# E-BookReaderSchematicUdateanuAndreea.net
KiCad netlist of a schematic drawn in EAGLE
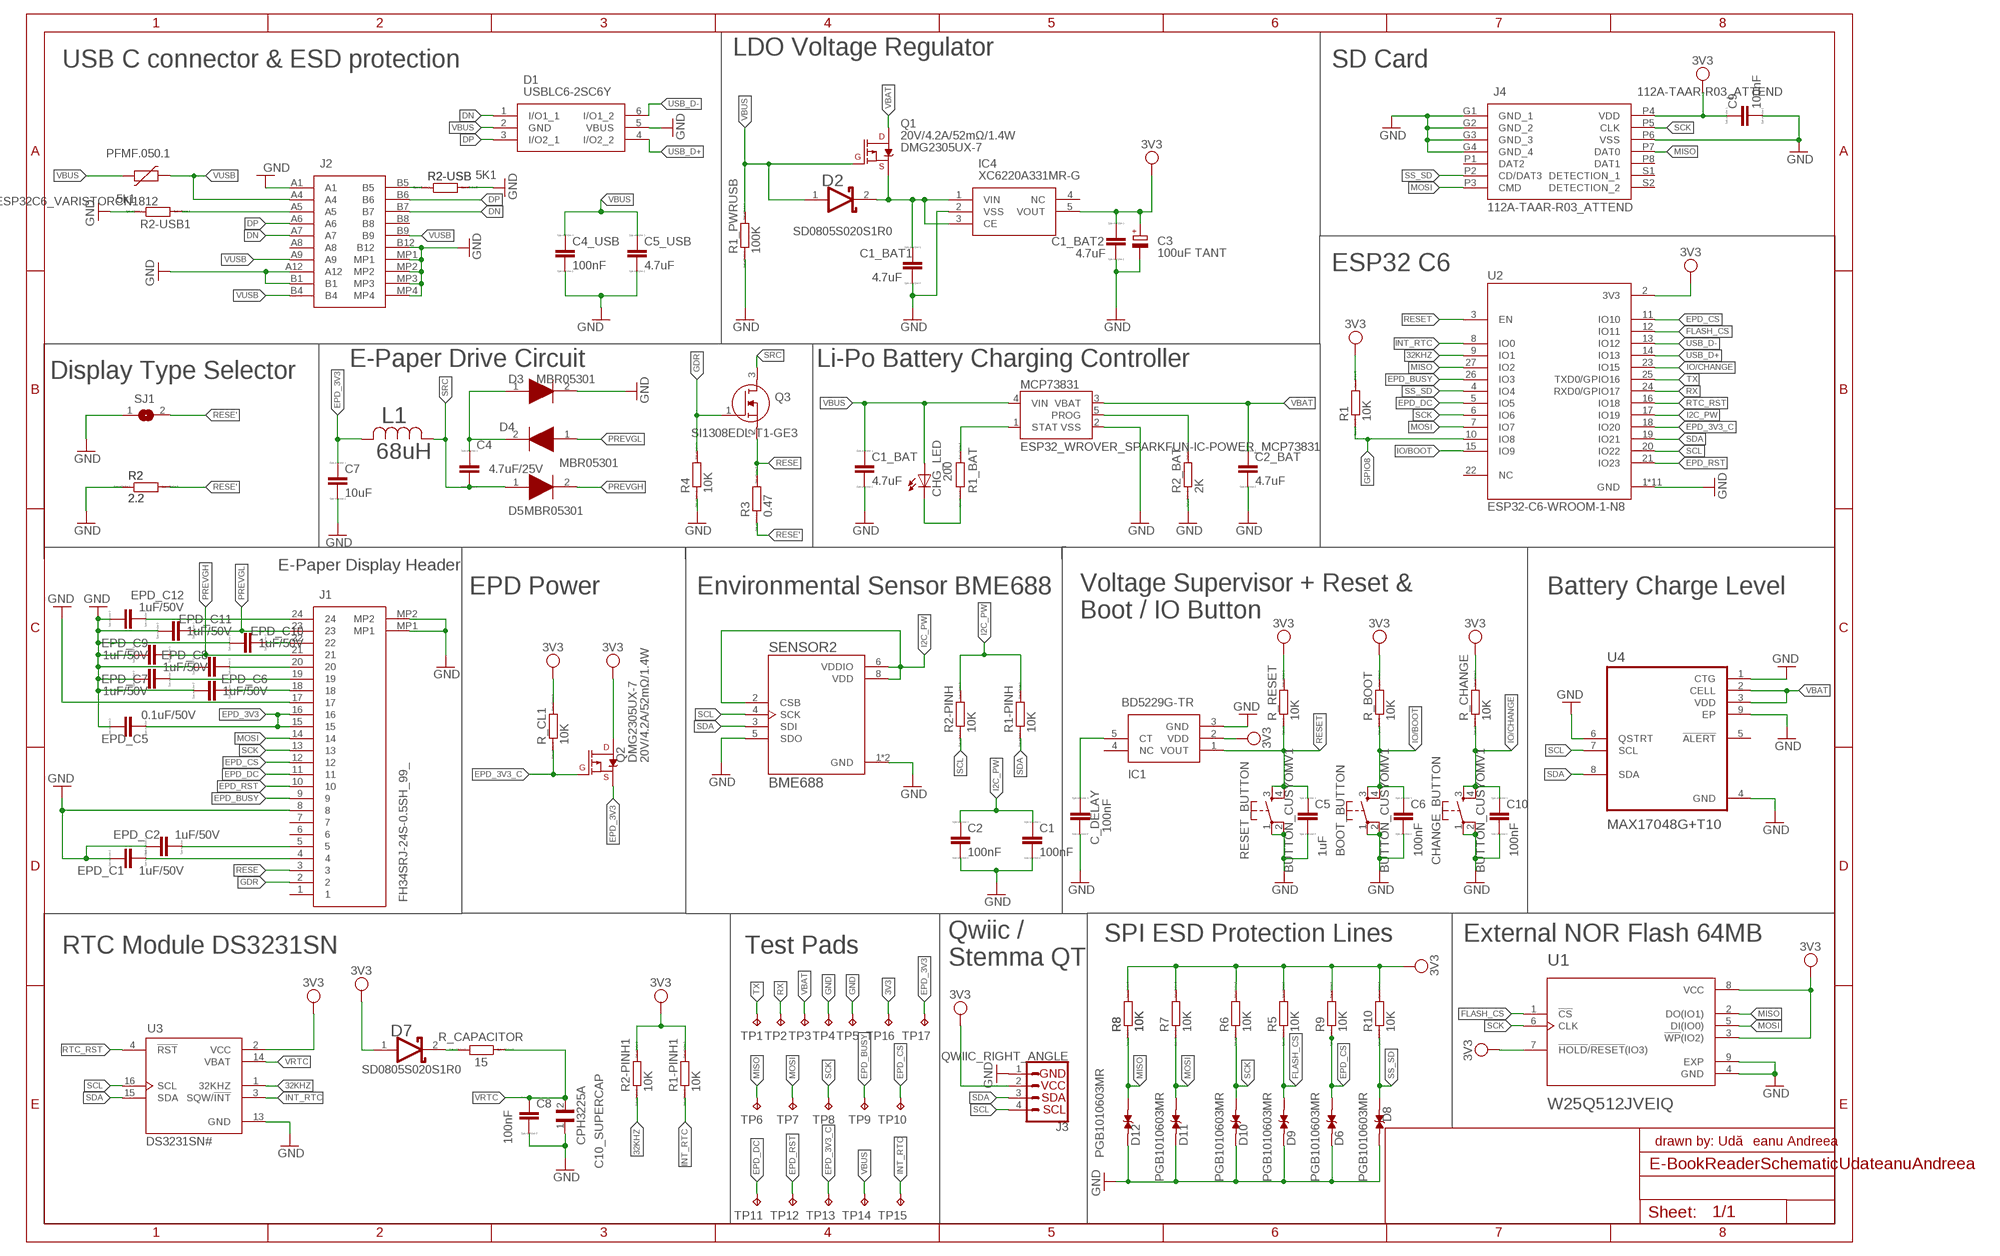
[diagram p0: schematic, sheet 1]

(export (version "E")
  (design (tool "Eeschema 10.0.6"))
  (components
    (comp (ref "BOOT_BUTTON")
      (value "BUTTON_CUSYOMV1")
      (footprint "eagle-import:MYBUTTON")
      (libsource (lib "eagle-import") (part "BUTTON_CUSYOMV1"))
    )
    (comp (ref "C1")
      (value "100nF")
      (footprint "eagle-import:EAGLE-LTSPICE_C0402")
      (libsource (lib "eagle-import") (part "EAGLE-LTSPICE_CC0402"))
    )
    (comp (ref "C1_BAT")
      (value "4.7uF")
      (footprint "eagle-import:EAGLE-LTSPICE_C0402")
      (libsource (lib "eagle-import") (part "EAGLE-LTSPICE_CC0402"))
    )
    (comp (ref "C1_BAT1")
      (value "4.7uF")
      (footprint "eagle-import:EAGLE-LTSPICE_C0402")
      (libsource (lib "eagle-import") (part "EAGLE-LTSPICE_CC0402"))
    )
    (comp (ref "C1_BAT2")
      (value "4.7uF")
      (footprint "eagle-import:EAGLE-LTSPICE_C0402")
      (libsource (lib "eagle-import") (part "EAGLE-LTSPICE_CC0402"))
    )
    (comp (ref "C2")
      (value "100nF")
      (footprint "eagle-import:EAGLE-LTSPICE_C0402")
      (libsource (lib "eagle-import") (part "EAGLE-LTSPICE_CC0402"))
    )
    (comp (ref "C2_BAT")
      (value "4.7uF")
      (footprint "eagle-import:EAGLE-LTSPICE_C0402")
      (libsource (lib "eagle-import") (part "EAGLE-LTSPICE_CC0402"))
    )
    (comp (ref "C3")
      (value "100uF TANT")
      (footprint "eagle-import:RCL_CT3528")
      (libsource (lib "eagle-import") (part "RCL_CPOL-EUCT3528"))
    )
    (comp (ref "C4")
      (value "4.7uF/25V")
      (footprint "eagle-import:EAGLE-LTSPICE_C0402")
      (libsource (lib "eagle-import") (part "EAGLE-LTSPICE_CC0402"))
    )
    (comp (ref "C4_USB")
      (value "100nF")
      (footprint "eagle-import:ESP32_WROVER_EAGLE-LTSPICE_C0402")
      (libsource (lib "eagle-import") (part "ESP32_WROVER_EAGLE-LTSPICE_CC0402"))
    )
    (comp (ref "C5")
      (value "1uF")
      (footprint "eagle-import:EAGLE-LTSPICE_C0402")
      (libsource (lib "eagle-import") (part "EAGLE-LTSPICE_CC0402"))
    )
    (comp (ref "C5_USB")
      (value "4.7uF")
      (footprint "eagle-import:ESP32_WROVER_EAGLE-LTSPICE_C0402")
      (libsource (lib "eagle-import") (part "ESP32_WROVER_EAGLE-LTSPICE_CC0402"))
    )
    (comp (ref "C6")
      (value "100nF")
      (footprint "eagle-import:EAGLE-LTSPICE_C0402")
      (libsource (lib "eagle-import") (part "EAGLE-LTSPICE_CC0402"))
    )
    (comp (ref "C7")
      (value "10uF")
      (footprint "eagle-import:EAGLE-LTSPICE_C0402")
      (libsource (lib "eagle-import") (part "EAGLE-LTSPICE_CC0402"))
    )
    (comp (ref "C8")
      (value "100nF")
      (footprint "eagle-import:EAGLE-LTSPICE_C0402")
      (libsource (lib "eagle-import") (part "EAGLE-LTSPICE_CC0402"))
    )
    (comp (ref "C9")
      (value "100nF")
      (footprint "eagle-import:ESP32_WROVER_EAGLE-LTSPICE_C0402")
      (libsource (lib "eagle-import") (part "ESP32_WROVER_EAGLE-LTSPICE_CC0402"))
    )
    (comp (ref "C10")
      (value "100nF")
      (footprint "eagle-import:EAGLE-LTSPICE_C0402")
      (libsource (lib "eagle-import") (part "EAGLE-LTSPICE_CC0402"))
    )
    (comp (ref "C10_SUPERCAP")
      (value "CPH3225A")
      (footprint "eagle-import:CAPCP3225X100N")
      (fields (field (name "MF") "Seiko Instruments"))
      (libsource (lib "eagle-import") (part "CPH3225A"))
    )
    (comp (ref "CHANGE_BUTTON")
      (value "BUTTON_CUSYOMV1")
      (footprint "eagle-import:MYBUTTON")
      (libsource (lib "eagle-import") (part "BUTTON_CUSYOMV1"))
    )
    (comp (ref "CHG_LED")
      (value "ADAFRUIT_LEDCHIP-LED0603")
      (footprint "eagle-import:ADAFRUIT_CHIP-LED0603")
      (libsource (lib "eagle-import") (part "ADAFRUIT_LEDCHIP-LED0603"))
    )
    (comp (ref "C_DELAY")
      (value "100nF")
      (footprint "eagle-import:EAGLE-LTSPICE_C0402")
      (libsource (lib "eagle-import") (part "EAGLE-LTSPICE_CC0402"))
    )
    (comp (ref "D1")
      (value "USBLC6-2SC6Y")
      (footprint "eagle-import:SOT95P280X145-6N")
      (fields (field (name "MF") "STMicroelectronics"))
      (libsource (lib "eagle-import") (part "USBLC6-2SC6Y"))
    )
    (comp (ref "D2")
      (value "SD0805S020S1R0")
      (footprint "eagle-import:ESP32_WROVER_AVX---SD0805S020S1R0_AVX_SD0805S020S1R0_0")
      (libsource (lib "eagle-import") (part "ESP32_WROVER_AVX---SD0805S020S1R0_AVX_SD0805S020S1R0_0_0"))
    )
    (comp (ref "D3")
      (value "MBR05301")
      (footprint "eagle-import:SOD3716X135N")
      (libsource (lib "eagle-import") (part "MBR05301"))
    )
    (comp (ref "D4")
      (value "MBR05301")
      (footprint "eagle-import:SOD3716X135N")
      (libsource (lib "eagle-import") (part "MBR05301"))
    )
    (comp (ref "D5")
      (value "MBR05301")
      (footprint "eagle-import:SOD3716X135N")
      (libsource (lib "eagle-import") (part "MBR05301"))
    )
    (comp (ref "D6")
      (value "PGB1010603MR")
      (footprint "eagle-import:DIOC1608X36N")
      (fields (field (name "MF") "Littelfuse Inc."))
      (libsource (lib "eagle-import") (part "PGB1010603MR"))
    )
    (comp (ref "D7")
      (value "SD0805S020S1R0")
      (footprint "eagle-import:ESP32_WROVER_AVX---SD0805S020S1R0_AVX_SD0805S020S1R0_0")
      (libsource (lib "eagle-import") (part "ESP32_WROVER_AVX---SD0805S020S1R0_AVX_SD0805S020S1R0_0_0"))
    )
    (comp (ref "D8")
      (value "PGB1010603MR")
      (footprint "eagle-import:DIOC1608X36N")
      (fields (field (name "MF") "Littelfuse Inc."))
      (libsource (lib "eagle-import") (part "PGB1010603MR"))
    )
    (comp (ref "D9")
      (value "PGB1010603MR")
      (footprint "eagle-import:DIOC1608X36N")
      (fields (field (name "MF") "Littelfuse Inc."))
      (libsource (lib "eagle-import") (part "PGB1010603MR"))
    )
    (comp (ref "D10")
      (value "PGB1010603MR")
      (footprint "eagle-import:DIOC1608X36N")
      (fields (field (name "MF") "Littelfuse Inc."))
      (libsource (lib "eagle-import") (part "PGB1010603MR"))
    )
    (comp (ref "D11")
      (value "PGB1010603MR")
      (footprint "eagle-import:DIOC1608X36N")
      (fields (field (name "MF") "Littelfuse Inc."))
      (libsource (lib "eagle-import") (part "PGB1010603MR"))
    )
    (comp (ref "D12")
      (value "PGB1010603MR")
      (footprint "eagle-import:DIOC1608X36N")
      (fields (field (name "MF") "Littelfuse Inc."))
      (libsource (lib "eagle-import") (part "PGB1010603MR"))
    )
    (comp (ref "EPD_C1")
      (value "1uF/50V")
      (footprint "eagle-import:EAGLE-LTSPICE_C0402")
      (libsource (lib "eagle-import") (part "EAGLE-LTSPICE_CC0402"))
    )
    (comp (ref "EPD_C2")
      (value "1uF/50V")
      (footprint "eagle-import:EAGLE-LTSPICE_C0402")
      (libsource (lib "eagle-import") (part "EAGLE-LTSPICE_CC0402"))
    )
    (comp (ref "EPD_C5")
      (value "0.1uF/50V")
      (footprint "eagle-import:EAGLE-LTSPICE_C0402")
      (libsource (lib "eagle-import") (part "EAGLE-LTSPICE_CC0402"))
    )
    (comp (ref "EPD_C6")
      (value "1uF/50V")
      (footprint "eagle-import:EAGLE-LTSPICE_C0402")
      (libsource (lib "eagle-import") (part "EAGLE-LTSPICE_CC0402"))
    )
    (comp (ref "EPD_C7")
      (value "1uF/50V")
      (footprint "eagle-import:EAGLE-LTSPICE_C0402")
      (libsource (lib "eagle-import") (part "EAGLE-LTSPICE_CC0402"))
    )
    (comp (ref "EPD_C8")
      (value "1uF/50V")
      (footprint "eagle-import:EAGLE-LTSPICE_C0402")
      (libsource (lib "eagle-import") (part "EAGLE-LTSPICE_CC0402"))
    )
    (comp (ref "EPD_C9")
      (value "1uF/50V")
      (footprint "eagle-import:EAGLE-LTSPICE_C0402")
      (libsource (lib "eagle-import") (part "EAGLE-LTSPICE_CC0402"))
    )
    (comp (ref "EPD_C10")
      (value "1uF/50V")
      (footprint "eagle-import:EAGLE-LTSPICE_C0402")
      (libsource (lib "eagle-import") (part "EAGLE-LTSPICE_CC0402"))
    )
    (comp (ref "EPD_C11")
      (value "1uF/50V")
      (footprint "eagle-import:EAGLE-LTSPICE_C0402")
      (libsource (lib "eagle-import") (part "EAGLE-LTSPICE_CC0402"))
    )
    (comp (ref "EPD_C12")
      (value "1uF/50V")
      (footprint "eagle-import:EAGLE-LTSPICE_C0402")
      (libsource (lib "eagle-import") (part "EAGLE-LTSPICE_CC0402"))
    )
    (comp (ref "IC1")
      (value "BD5229G-TR")
      (footprint "eagle-import:SOT95P280X125-5N")
      (fields (field (name "MOUSER_PART_NUMBER") "755-BD5229G-TR"))
      (libsource (lib "eagle-import") (part "BD5229G-TR"))
    )
    (comp (ref "IC4")
      (value "XC6220A331MR-G")
      (footprint "eagle-import:SOT95P280X120-5N")
      (fields (field (name "MOUSER_PART_NUMBER") "865-XC6220A331MR-G"))
      (libsource (lib "eagle-import") (part "XC6220A331MR-G"))
    )
    (comp (ref "J1")
      (value "FH34SRJ-24S-0.5SH_99_")
      (footprint "eagle-import:FH34SRJ24S05SH99")
      (fields
        (field (name "MANUFACTURER_PART_NUMBER") "FH34SRJ-24S-0.5SH(99)")
        (field (name "MOUSER_PART_NUMBER") "798-FH34SRJ24S05SH99")
      )
      (libsource (lib "eagle-import") (part "FH34SRJ-24S-0.5SH_99_"))
    )
    (comp (ref "J2")
      (value "SAMACSYS_PARTS_USB4110-GF-A")
      (footprint "eagle-import:SAMACSYS_PARTS_USB4110GFA")
      (fields
        (field (name "MANUFACTURER_PART_NUMBER") "USB4110-GF-A")
        (field (name "MOUSER_PART_NUMBER") "640-USB4110-GF-A")
      )
      (libsource (lib "eagle-import") (part "SAMACSYS_PARTS_USB4110-GF-A"))
    )
    (comp (ref "J3")
      (value "QWIIC_RIGHT_ANGLE")
      (footprint "eagle-import:JST04_1MM_RA")
      (libsource (lib "eagle-import") (part "QWIIC_CONNECTORJS-1MM"))
    )
    (comp (ref "J4")
      (value "112A-TAAR-R03_ATTEND")
      (footprint "eagle-import:112ATAARR03ATTEND")
      (fields (field (name "MANUFACTURER_PART_NUMBER") "112A-TAAR-R03 ATTEND"))
      (libsource (lib "eagle-import") (part "112A-TAAR-R03_ATTEND"))
    )
    (comp (ref "L1")
      (value "68uH")
      (footprint "eagle-import:IND_4828-WE-TPC_WRE")
      (fields
        (field (name "MANUFACTURER_PART_NUMBER") "744043680")
        (field (name "COPYRIGHT") "Copyright (C) 2024 Ultra Librarian. All rights reserved.")
      )
      (libsource (lib "eagle-import") (part "744043680IND_4828-WE-TPC_WRE"))
    )
    (comp (ref "MCP73831")
      (value "ESP32_WROVER_SPARKFUN-IC-POWER_MCP73831")
      (footprint "eagle-import:ESP32_WROVER_SPARKFUN-IC-POWER_SOT23-5")
      (libsource (lib "eagle-import") (part "ESP32_WROVER_SPARKFUN-IC-POWER_MCP73831"))
    )
    (comp (ref "PFMF.050.1")
      (value "ESP32C6_VARISTORCN1812")
      (footprint "eagle-import:ESP32C6_VARISTOR_CT_CN1812")
      (libsource (lib "eagle-import") (part "ESP32C6_VARISTORCN1812"))
    )
    (comp (ref "Q1")
      (value "20V/4.2A/52mΩ/1.4W")
      (footprint "eagle-import:ESP32_WROVER_SPARKFUN-DISCRETESEMI_SOT23-3")
      (libsource (lib "eagle-import") (part "ESP32_WROVER_SPARKFUN-DISCRETESEMI_MOSFET_PCH-DMG2305UX-7"))
    )
    (comp (ref "Q2")
      (value "20V/4.2A/52mΩ/1.4W")
      (footprint "eagle-import:ESP32_WROVER_SPARKFUN-DISCRETESEMI_SOT23-3")
      (libsource (lib "eagle-import") (part "ESP32_WROVER_SPARKFUN-DISCRETESEMI_MOSFET_PCH-DMG2305UX-7"))
    )
    (comp (ref "Q3")
      (value "SI1308EDL-T1-GE3")
      (footprint "eagle-import:SOT65P210X110-3N")
      (fields (field (name "MF") "Vishay Siliconix"))
      (libsource (lib "eagle-import") (part "SI1308EDL-T1-GE3"))
    )
    (comp (ref "R1")
      (value "10K")
      (footprint "eagle-import:ESP32_WROVER_EAGLE-LTSPICE_R0402")
      (libsource (lib "eagle-import") (part "ESP32_WROVER_EAGLE-LTSPICE_RR0402"))
    )
    (comp (ref "R1-PINH")
      (value "10K")
      (footprint "eagle-import:ESP32_WROVER_EAGLE-LTSPICE_R0402")
      (libsource (lib "eagle-import") (part "ESP32_WROVER_EAGLE-LTSPICE_RR0402"))
    )
    (comp (ref "R1-PINH1")
      (value "10K")
      (footprint "eagle-import:ESP32_WROVER_EAGLE-LTSPICE_R0402")
      (libsource (lib "eagle-import") (part "ESP32_WROVER_EAGLE-LTSPICE_RR0402"))
    )
    (comp (ref "R1_BAT")
      (value "200")
      (footprint "eagle-import:ESP32_WROVER_EAGLE-LTSPICE_R0402")
      (libsource (lib "eagle-import") (part "ESP32_WROVER_EAGLE-LTSPICE_RR0402"))
    )
    (comp (ref "R1_PWRUSB")
      (value "100K")
      (footprint "eagle-import:ESP32_WROVER_EAGLE-LTSPICE_R0402")
      (libsource (lib "eagle-import") (part "ESP32_WROVER_EAGLE-LTSPICE_RR0402"))
    )
    (comp (ref "R2")
      (value "2.2")
      (footprint "eagle-import:ESP32_WROVER_EAGLE-LTSPICE_R0402")
      (libsource (lib "eagle-import") (part "ESP32_WROVER_EAGLE-LTSPICE_RR0402"))
    )
    (comp (ref "R2-PINH")
      (value "10K")
      (footprint "eagle-import:ESP32_WROVER_EAGLE-LTSPICE_R0402")
      (libsource (lib "eagle-import") (part "ESP32_WROVER_EAGLE-LTSPICE_RR0402"))
    )
    (comp (ref "R2-PINH1")
      (value "10K")
      (footprint "eagle-import:ESP32_WROVER_EAGLE-LTSPICE_R0402")
      (libsource (lib "eagle-import") (part "ESP32_WROVER_EAGLE-LTSPICE_RR0402"))
    )
    (comp (ref "R2-USB")
      (value "5K1")
      (footprint "eagle-import:ESP32_WROVER_EAGLE-LTSPICE_R0402")
      (libsource (lib "eagle-import") (part "ESP32_WROVER_EAGLE-LTSPICE_RR0402"))
    )
    (comp (ref "R2-USB1")
      (value "5k1")
      (footprint "eagle-import:ESP32_WROVER_EAGLE-LTSPICE_R0402")
      (libsource (lib "eagle-import") (part "ESP32_WROVER_EAGLE-LTSPICE_RR0402"))
    )
    (comp (ref "R2_BAT")
      (value "2K")
      (footprint "eagle-import:ESP32_WROVER_EAGLE-LTSPICE_R0402")
      (libsource (lib "eagle-import") (part "ESP32_WROVER_EAGLE-LTSPICE_RR0402"))
    )
    (comp (ref "R3")
      (value "0.47")
      (footprint "eagle-import:ESP32_WROVER_EAGLE-LTSPICE_R0402")
      (libsource (lib "eagle-import") (part "ESP32_WROVER_EAGLE-LTSPICE_RR0402"))
    )
    (comp (ref "R4")
      (value "10K")
      (footprint "eagle-import:ESP32_WROVER_EAGLE-LTSPICE_R0402")
      (libsource (lib "eagle-import") (part "ESP32_WROVER_EAGLE-LTSPICE_RR0402"))
    )
    (comp (ref "R5")
      (value "10K")
      (footprint "eagle-import:ESP32_WROVER_EAGLE-LTSPICE_R0402")
      (libsource (lib "eagle-import") (part "ESP32_WROVER_EAGLE-LTSPICE_RR0402"))
    )
    (comp (ref "R6")
      (value "10K")
      (footprint "eagle-import:ESP32_WROVER_EAGLE-LTSPICE_R0402")
      (libsource (lib "eagle-import") (part "ESP32_WROVER_EAGLE-LTSPICE_RR0402"))
    )
    (comp (ref "R7")
      (value "10K")
      (footprint "eagle-import:ESP32_WROVER_EAGLE-LTSPICE_R0402")
      (libsource (lib "eagle-import") (part "ESP32_WROVER_EAGLE-LTSPICE_RR0402"))
    )
    (comp (ref "R8")
      (value "10K")
      (footprint "eagle-import:ESP32_WROVER_EAGLE-LTSPICE_R0402")
      (libsource (lib "eagle-import") (part "ESP32_WROVER_EAGLE-LTSPICE_RR0402"))
    )
    (comp (ref "R9")
      (value "10K")
      (footprint "eagle-import:ESP32_WROVER_EAGLE-LTSPICE_R0402")
      (libsource (lib "eagle-import") (part "ESP32_WROVER_EAGLE-LTSPICE_RR0402"))
    )
    (comp (ref "R10")
      (value "10K")
      (footprint "eagle-import:ESP32_WROVER_EAGLE-LTSPICE_R0402")
      (libsource (lib "eagle-import") (part "ESP32_WROVER_EAGLE-LTSPICE_RR0402"))
    )
    (comp (ref "RESET_BUTTON")
      (value "BUTTON_CUSYOMV1")
      (footprint "eagle-import:MYBUTTON")
      (libsource (lib "eagle-import") (part "BUTTON_CUSYOMV1"))
    )
    (comp (ref "R_BOOT")
      (value "10K")
      (footprint "eagle-import:ESP32_WROVER_EAGLE-LTSPICE_R0402")
      (libsource (lib "eagle-import") (part "ESP32_WROVER_EAGLE-LTSPICE_RR0402"))
    )
    (comp (ref "R_CAPACITOR")
      (value "15")
      (footprint "eagle-import:ESP32_WROVER_EAGLE-LTSPICE_R0402")
      (libsource (lib "eagle-import") (part "ESP32_WROVER_EAGLE-LTSPICE_RR0402"))
    )
    (comp (ref "R_CHANGE")
      (value "10K")
      (footprint "eagle-import:ESP32_WROVER_EAGLE-LTSPICE_R0402")
      (libsource (lib "eagle-import") (part "ESP32_WROVER_EAGLE-LTSPICE_RR0402"))
    )
    (comp (ref "R_CL1")
      (value "10K")
      (footprint "eagle-import:ESP32_WROVER_EAGLE-LTSPICE_R0402")
      (libsource (lib "eagle-import") (part "ESP32_WROVER_EAGLE-LTSPICE_RR0402"))
    )
    (comp (ref "R_RESET")
      (value "10K")
      (footprint "eagle-import:ESP32_WROVER_EAGLE-LTSPICE_R0402")
      (libsource (lib "eagle-import") (part "ESP32_WROVER_EAGLE-LTSPICE_RR0402"))
    )
    (comp (ref "SENSOR2")
      (value "BME688")
      (footprint "eagle-import:ESP32_WROVER_BME680_PSON80P300X300X100-8N")
      (fields (field (name "MF") "Bosch Sensortec") (field (name "MP") "BME680"))
      (libsource (lib "eagle-import") (part "ESP32_WROVER_BME680_BME680"))
    )
    (comp (ref "SJ1") (value "SJ") (footprint "eagle-import:SJ") (libsource (lib "eagle-import") (part "SJ")))
    (comp (ref "TP1")
      (value "TPTP20R")
      (footprint "eagle-import:TP20R")
      (libsource (lib "eagle-import") (part "TP"))
    )
    (comp (ref "TP2")
      (value "TP")
      (footprint "eagle-import:TP20R")
      (libsource (lib "eagle-import") (part "TP"))
    )
    (comp (ref "TP3")
      (value "TP")
      (footprint "eagle-import:TP20R")
      (libsource (lib "eagle-import") (part "TP"))
    )
    (comp (ref "TP4")
      (value "TP")
      (footprint "eagle-import:TP20R")
      (libsource (lib "eagle-import") (part "TP"))
    )
    (comp (ref "TP5")
      (value "TP")
      (footprint "eagle-import:TP20R")
      (libsource (lib "eagle-import") (part "TP"))
    )
    (comp (ref "TP6")
      (value "TP")
      (footprint "eagle-import:TP20R")
      (libsource (lib "eagle-import") (part "TP"))
    )
    (comp (ref "TP7")
      (value "TP")
      (footprint "eagle-import:TP20R")
      (libsource (lib "eagle-import") (part "TP"))
    )
    (comp (ref "TP8")
      (value "TP")
      (footprint "eagle-import:TP20R")
      (libsource (lib "eagle-import") (part "TP"))
    )
    (comp (ref "TP9")
      (value "TP")
      (footprint "eagle-import:TP20R")
      (libsource (lib "eagle-import") (part "TP"))
    )
    (comp (ref "TP10")
      (value "TP")
      (footprint "eagle-import:TP20R")
      (libsource (lib "eagle-import") (part "TP"))
    )
    (comp (ref "TP11")
      (value "TP")
      (footprint "eagle-import:TP20R")
      (libsource (lib "eagle-import") (part "TP"))
    )
    (comp (ref "TP12")
      (value "TP")
      (footprint "eagle-import:TP20R")
      (libsource (lib "eagle-import") (part "TP"))
    )
    (comp (ref "TP13")
      (value "TP")
      (footprint "eagle-import:TP20R")
      (libsource (lib "eagle-import") (part "TP"))
    )
    (comp (ref "TP14")
      (value "TP")
      (footprint "eagle-import:TP20R")
      (libsource (lib "eagle-import") (part "TP"))
    )
    (comp (ref "TP15")
      (value "TP")
      (footprint "eagle-import:TP20R")
      (libsource (lib "eagle-import") (part "TP"))
    )
    (comp (ref "TP16")
      (value "TP")
      (footprint "eagle-import:TP20R")
      (libsource (lib "eagle-import") (part "TP"))
    )
    (comp (ref "TP17")
      (value "TP")
      (footprint "eagle-import:TP20R")
      (libsource (lib "eagle-import") (part "TP"))
    )
    (comp (ref "U1")
      (value "W25Q512JVEIQ")
      (footprint "eagle-import:SON127P600X800X80-9N")
      (fields (field (name "MF") "Winbond Electronics"))
      (libsource (lib "eagle-import") (part "W25Q512JVEIQ"))
    )
    (comp (ref "U2")
      (value "ESP32-C6-WROOM-1-N8")
      (footprint "eagle-import:XCVR_ESP32-C6-WROOM-1-N8")
      (fields (field (name "MF") "Espressif Systems"))
      (libsource (lib "eagle-import") (part "ESP32-C6-WROOM-1-N8"))
    )
    (comp (ref "U3")
      (value "DS3231SN#")
      (footprint "eagle-import:SOIC127P1032X265-16N")
      (fields (field (name "MF") "Analog Devices"))
      (libsource (lib "eagle-import") (part "DS3231SN#"))
    )
    (comp (ref "U4")
      (value "MAX17048G+T10")
      (footprint "eagle-import:SON50P200X200X80-9N")
      (fields (field (name "MF") "Analog Devices"))
      (libsource (lib "eagle-import") (part "MAX17048G+T10"))
    )
  )
  (nets
    (net (code "1") (name "3V3") (class "Default")
      (node (ref "C1_BAT2") (pin "1") (pinfunction "1_1") (pintype "passive"))
      (node (ref "C3") (pin "+") (pinfunction "+_+") (pintype "passive"))
      (node (ref "C9") (pin "1") (pinfunction "1_1") (pintype "passive"))
      (node (ref "D7") (pin "1") (pinfunction "ANODE_1") (pintype "bidirectional"))
      (node (ref "IC1") (pin "2") (pinfunction "VDD_2") (pintype "bidirectional"))
      (node (ref "IC4") (pin "5") (pinfunction "VOUT_5") (pintype "bidirectional"))
      (node (ref "J3") (pin "2") (pinfunction "2_2") (pintype "power_in"))
      (node (ref "J4") (pin "P4") (pinfunction "VDD_P4") (pintype "bidirectional"))
      (node (ref "Q2") (pin "3") (pinfunction "D_3") (pintype "bidirectional"))
      (node (ref "R1") (pin "2") (pinfunction "2_2") (pintype "passive"))
      (node (ref "R1-PINH1") (pin "2") (pinfunction "2_2") (pintype "passive"))
      (node (ref "R10") (pin "2") (pinfunction "2_2") (pintype "passive"))
      (node (ref "R2-PINH1") (pin "2") (pinfunction "2_2") (pintype "passive"))
      (node (ref "R5") (pin "2") (pinfunction "2_2") (pintype "passive"))
      (node (ref "R6") (pin "2") (pinfunction "2_2") (pintype "passive"))
      (node (ref "R7") (pin "2") (pinfunction "2_2") (pintype "passive"))
      (node (ref "R8") (pin "2") (pinfunction "2_2") (pintype "passive"))
      (node (ref "R9") (pin "2") (pinfunction "2_2") (pintype "passive"))
      (node (ref "R_BOOT") (pin "2") (pinfunction "2_2") (pintype "passive"))
      (node (ref "R_CHANGE") (pin "2") (pinfunction "2_2") (pintype "passive"))
      (node (ref "R_CL1") (pin "2") (pinfunction "2_2") (pintype "passive"))
      (node (ref "R_RESET") (pin "2") (pinfunction "2_2") (pintype "passive"))
      (node (ref "TP16") (pin "TP") (pinfunction "TP_TP") (pintype "input"))
      (node (ref "U1") (pin "3") (pinfunction "~{WP}(IO2)_3") (pintype "bidirectional"))
      (node (ref "U1") (pin "7") (pinfunction "~{HOLD}/~{RESET}(IO3)_7") (pintype "bidirectional"))
      (node (ref "U1") (pin "8") (pinfunction "VCC_8") (pintype "power_in"))
      (node (ref "U2") (pin "2") (pinfunction "3V3_2") (pintype "power_in"))
      (node (ref "U3") (pin "2") (pinfunction "VCC_2") (pintype "power_in"))
    )
    (net (code "2") (name "32KHZ") (class "Default")
      (node (ref "R2-PINH1") (pin "1") (pinfunction "1_1") (pintype "passive"))
      (node (ref "U2") (pin "9") (pinfunction "IO1_9") (pintype "bidirectional"))
      (node (ref "U3") (pin "1") (pinfunction "32KHZ_1") (pintype "output"))
    )
    (net (code "3") (name "DN") (class "Default")
      (node (ref "D1") (pin "1") (pinfunction "I/O1_1_1") (pintype "bidirectional"))
      (node (ref "J2") (pin "A7") (pinfunction "A7_A7") (pintype "bidirectional"))
      (node (ref "J2") (pin "B7") (pinfunction "B7_B7") (pintype "bidirectional"))
    )
    (net (code "4") (name "DP") (class "Default")
      (node (ref "D1") (pin "3") (pinfunction "I/O2_1_3") (pintype "bidirectional"))
      (node (ref "J2") (pin "A6") (pinfunction "A6_A6") (pintype "bidirectional"))
      (node (ref "J2") (pin "B6") (pinfunction "B6_B6") (pintype "bidirectional"))
    )
    (net (code "5") (name "EPD_3V3") (class "Default")
      (node (ref "C7") (pin "1") (pinfunction "1_1") (pintype "passive"))
      (node (ref "EPD_C5") (pin "1") (pinfunction "1_1") (pintype "passive"))
      (node (ref "J1") (pin "15") (pinfunction "15_15") (pintype "bidirectional"))
      (node (ref "J1") (pin "16") (pinfunction "16_16") (pintype "bidirectional"))
      (node (ref "L1") (pin "2") (pinfunction "2_2") (pintype "passive"))
      (node (ref "Q2") (pin "2") (pinfunction "S_2") (pintype "bidirectional"))
      (node (ref "TP17") (pin "TP") (pinfunction "TP_TP") (pintype "input"))
    )
    (net (code "6") (name "EPD_3V3_C") (class "Default")
      (node (ref "Q2") (pin "1") (pinfunction "G_1") (pintype "bidirectional"))
      (node (ref "R_CL1") (pin "1") (pinfunction "1_1") (pintype "passive"))
      (node (ref "TP13") (pin "TP") (pinfunction "TP_TP") (pintype "input"))
      (node (ref "U2") (pin "18") (pinfunction "IO20_18") (pintype "bidirectional"))
    )
    (net (code "7") (name "EPD_BUSY") (class "Default")
      (node (ref "J1") (pin "9") (pinfunction "9_9") (pintype "bidirectional"))
      (node (ref "TP9") (pin "TP") (pinfunction "TP_TP") (pintype "input"))
      (node (ref "U2") (pin "26") (pinfunction "IO3_26") (pintype "bidirectional"))
    )
    (net (code "8") (name "EPD_CS") (class "Default")
      (node (ref "D6") (pin "2") (pinfunction "2_2") (pintype "passive"))
      (node (ref "J1") (pin "12") (pinfunction "12_12") (pintype "bidirectional"))
      (node (ref "R9") (pin "1") (pinfunction "1_1") (pintype "passive"))
      (node (ref "TP10") (pin "TP") (pinfunction "TP_TP") (pintype "input"))
      (node (ref "U2") (pin "11") (pinfunction "IO10_11") (pintype "bidirectional"))
    )
    (net (code "9") (name "EPD_DC") (class "Default")
      (node (ref "J1") (pin "11") (pinfunction "11_11") (pintype "bidirectional"))
      (node (ref "TP11") (pin "TP") (pinfunction "TP_TP") (pintype "input"))
      (node (ref "U2") (pin "5") (pinfunction "IO5_5") (pintype "bidirectional"))
    )
    (net (code "10") (name "EPD_RST") (class "Default")
      (node (ref "J1") (pin "10") (pinfunction "10_10") (pintype "bidirectional"))
      (node (ref "TP12") (pin "TP") (pinfunction "TP_TP") (pintype "input"))
      (node (ref "U2") (pin "21") (pinfunction "IO23_21") (pintype "bidirectional"))
    )
    (net (code "11") (name "FLASH_CS") (class "Default")
      (node (ref "D9") (pin "2") (pinfunction "2_2") (pintype "passive"))
      (node (ref "R5") (pin "1") (pinfunction "1_1") (pintype "passive"))
      (node (ref "U1") (pin "1") (pinfunction "~{CS}_1") (pintype "input"))
      (node (ref "U2") (pin "12") (pinfunction "IO11_12") (pintype "bidirectional"))
    )
    (net (code "12") (name "GDR") (class "Default")
      (node (ref "J1") (pin "2") (pinfunction "2_2") (pintype "bidirectional"))
      (node (ref "Q3") (pin "1") (pinfunction "G_1") (pintype "bidirectional"))
      (node (ref "R4") (pin "2") (pinfunction "2_2") (pintype "passive"))
    )
    (net (code "13") (name "GND") (class "Default")
      (node (ref "BOOT_BUTTON") (pin "1") (pinfunction "1_1") (pintype "passive"))
      (node (ref "BOOT_BUTTON") (pin "2") (pinfunction "2_2") (pintype "passive"))
      (node (ref "C1") (pin "2") (pinfunction "2_2") (pintype "passive"))
      (node (ref "C10") (pin "2") (pinfunction "2_2") (pintype "passive"))
      (node (ref "C10_SUPERCAP") (pin "1") (pinfunction "1_1") (pintype "passive"))
      (node (ref "C1_BAT") (pin "2") (pinfunction "2_2") (pintype "passive"))
      (node (ref "C1_BAT1") (pin "2") (pinfunction "2_2") (pintype "passive"))
      (node (ref "C1_BAT2") (pin "2") (pinfunction "2_2") (pintype "passive"))
      (node (ref "C2") (pin "2") (pinfunction "2_2") (pintype "passive"))
      (node (ref "C2_BAT") (pin "2") (pinfunction "2_2") (pintype "passive"))
      (node (ref "C3") (pin "-") (pinfunction "-_-") (pintype "passive"))
      (node (ref "C4_USB") (pin "2") (pinfunction "2_2") (pintype "passive"))
      (node (ref "C5") (pin "2") (pinfunction "2_2") (pintype "passive"))
      (node (ref "C5_USB") (pin "2") (pinfunction "2_2") (pintype "passive"))
      (node (ref "C6") (pin "2") (pinfunction "2_2") (pintype "passive"))
      (node (ref "C7") (pin "2") (pinfunction "2_2") (pintype "passive"))
      (node (ref "C8") (pin "2") (pinfunction "2_2") (pintype "passive"))
      (node (ref "C9") (pin "2") (pinfunction "2_2") (pintype "passive"))
      (node (ref "CHANGE_BUTTON") (pin "1") (pinfunction "1_1") (pintype "passive"))
      (node (ref "CHANGE_BUTTON") (pin "2") (pinfunction "2_2") (pintype "passive"))
      (node (ref "C_DELAY") (pin "2") (pinfunction "2_2") (pintype "passive"))
      (node (ref "D1") (pin "5") (pinfunction "VBUS_5") (pintype "bidirectional"))
      (node (ref "D10") (pin "1") (pinfunction "1_1") (pintype "passive"))
      (node (ref "D11") (pin "1") (pinfunction "1_1") (pintype "passive"))
      (node (ref "D12") (pin "1") (pinfunction "1_1") (pintype "passive"))
      (node (ref "D3") (pin "2") (pinfunction "K_2") (pintype "bidirectional"))
      (node (ref "D6") (pin "1") (pinfunction "1_1") (pintype "passive"))
      (node (ref "D8") (pin "1") (pinfunction "1_1") (pintype "passive"))
      (node (ref "D9") (pin "1") (pinfunction "1_1") (pintype "passive"))
      (node (ref "EPD_C1") (pin "2") (pinfunction "2_2") (pintype "passive"))
      (node (ref "EPD_C10") (pin "2") (pinfunction "2_2") (pintype "passive"))
      (node (ref "EPD_C11") (pin "2") (pinfunction "2_2") (pintype "passive"))
      (node (ref "EPD_C12") (pin "2") (pinfunction "2_2") (pintype "passive"))
      (node (ref "EPD_C2") (pin "2") (pinfunction "2_2") (pintype "passive"))
      (node (ref "EPD_C5") (pin "2") (pinfunction "2_2") (pintype "passive"))
      (node (ref "EPD_C6") (pin "2") (pinfunction "2_2") (pintype "passive"))
      (node (ref "EPD_C7") (pin "2") (pinfunction "2_2") (pintype "passive"))
      (node (ref "EPD_C8") (pin "2") (pinfunction "2_2") (pintype "passive"))
      (node (ref "EPD_C9") (pin "2") (pinfunction "2_2") (pintype "passive"))
      (node (ref "IC1") (pin "3") (pinfunction "GND_3") (pintype "bidirectional"))
      (node (ref "IC4") (pin "2") (pinfunction "VSS_2") (pintype "bidirectional"))
      (node (ref "J1") (pin "17") (pinfunction "17_17") (pintype "bidirectional"))
      (node (ref "J1") (pin "8") (pinfunction "8_8") (pintype "bidirectional"))
      (node (ref "J1") (pin "MP1") (pinfunction "MP1_MP1") (pintype "bidirectional"))
      (node (ref "J1") (pin "MP2") (pinfunction "MP2_MP2") (pintype "bidirectional"))
      (node (ref "J2") (pin "A1") (pinfunction "A1_A1") (pintype "bidirectional"))
      (node (ref "J2") (pin "A12") (pinfunction "A12_A12") (pintype "bidirectional"))
      (node (ref "J2") (pin "B1") (pinfunction "B1_B1") (pintype "bidirectional"))
      (node (ref "J2") (pin "B12") (pinfunction "B12_B12") (pintype "bidirectional"))
      (node (ref "J2") (pin "MP1") (pinfunction "MP1_MP1") (pintype "bidirectional"))
      (node (ref "J2") (pin "MP2") (pinfunction "MP2_MP2") (pintype "bidirectional"))
      (node (ref "J2") (pin "MP3") (pinfunction "MP3_MP3") (pintype "bidirectional"))
      (node (ref "J2") (pin "MP4") (pinfunction "MP4_MP4") (pintype "bidirectional"))
      (node (ref "J3") (pin "1") (pinfunction "1_1") (pintype "power_in"))
      (node (ref "J4") (pin "G1") (pinfunction "GND_1_G1") (pintype "bidirectional"))
      (node (ref "J4") (pin "G2") (pinfunction "GND_2_G2") (pintype "bidirectional"))
      (node (ref "J4") (pin "G3") (pinfunction "GND_3_G3") (pintype "bidirectional"))
      (node (ref "J4") (pin "G4") (pinfunction "GND_4_G4") (pintype "bidirectional"))
      (node (ref "J4") (pin "P6") (pinfunction "VSS_P6") (pintype "bidirectional"))
      (node (ref "MCP73831") (pin "2") (pinfunction "VSS_2") (pintype "power_in"))
      (node (ref "R1_PWRUSB") (pin "1") (pinfunction "1_1") (pintype "passive"))
      (node (ref "R2") (pin "1") (pinfunction "1_1") (pintype "passive"))
      (node (ref "R2-USB") (pin "2") (pinfunction "2_2") (pintype "passive"))
      (node (ref "R2-USB1") (pin "1") (pinfunction "1_1") (pintype "passive"))
      (node (ref "R2_BAT") (pin "1") (pinfunction "1_1") (pintype "passive"))
      (node (ref "R4") (pin "1") (pinfunction "1_1") (pintype "passive"))
      (node (ref "RESET_BUTTON") (pin "1") (pinfunction "1_1") (pintype "passive"))
      (node (ref "RESET_BUTTON") (pin "2") (pinfunction "2_2") (pintype "passive"))
      (node (ref "SENSOR2") (pin "1") (pinfunction "GND_1") (pintype "power_in"))
      (node (ref "SENSOR2") (pin "5") (pinfunction "SDO_5") (pintype "bidirectional"))
      (node (ref "SENSOR2") (pin "7") (pinfunction "GND_7") (pintype "power_in"))
      (node (ref "SJ1") (pin "1") (pinfunction "1_1") (pintype "passive"))
      (node (ref "TP4") (pin "TP") (pinfunction "TP_TP") (pintype "input"))
      (node (ref "TP5") (pin "TP") (pinfunction "TP_TP") (pintype "input"))
      (node (ref "U1") (pin "4") (pinfunction "GND_4") (pintype "power_in"))
      (node (ref "U1") (pin "9") (pinfunction "EXP_9") (pintype "passive"))
      (node (ref "U2") (pin "1") (pinfunction "GND_1") (pintype "power_in"))
      (node (ref "U2") (pin "28") (pinfunction "GND_28") (pintype "power_in"))
      (node (ref "U2") (pin "29_1") (pinfunction "GND_29_1") (pintype "power_in"))
      (node (ref "U2") (pin "29_2") (pinfunction "GND_29_2") (pintype "power_in"))
      (node (ref "U2") (pin "29_3") (pinfunction "GND_29_3") (pintype "power_in"))
      (node (ref "U2") (pin "29_4") (pinfunction "GND_29_4") (pintype "power_in"))
      (node (ref "U2") (pin "29_5") (pinfunction "GND_29_5") (pintype "power_in"))
      (node (ref "U2") (pin "29_6") (pinfunction "GND_29_6") (pintype "power_in"))
      (node (ref "U2") (pin "29_7") (pinfunction "GND_29_7") (pintype "power_in"))
      (node (ref "U2") (pin "29_8") (pinfunction "GND_29_8") (pintype "power_in"))
      (node (ref "U2") (pin "29_9") (pinfunction "GND_29_9") (pintype "power_in"))
      (node (ref "U3") (pin "13") (pinfunction "GND_13") (pintype "power_in"))
      (node (ref "U4") (pin "1") (pinfunction "CTG_1") (pintype "power_in"))
      (node (ref "U4") (pin "4") (pinfunction "GND_4") (pintype "power_in"))
      (node (ref "U4") (pin "6") (pinfunction "QSTRT_6") (pintype "input"))
      (node (ref "U4") (pin "9") (pinfunction "EP_9") (pintype "power_in"))
    )
    (net (code "14") (name "GPIO8") (class "Default")
      (node (ref "R1") (pin "1") (pinfunction "1_1") (pintype "passive"))
      (node (ref "U2") (pin "10") (pinfunction "IO8_10") (pintype "bidirectional"))
    )
    (net (code "15") (name "I2C_PW") (class "Default")
      (node (ref "C1") (pin "1") (pinfunction "1_1") (pintype "passive"))
      (node (ref "C2") (pin "1") (pinfunction "1_1") (pintype "passive"))
      (node (ref "R1-PINH") (pin "2") (pinfunction "2_2") (pintype "passive"))
      (node (ref "R2-PINH") (pin "2") (pinfunction "2_2") (pintype "passive"))
      (node (ref "SENSOR2") (pin "2") (pinfunction "CSB_2") (pintype "input"))
      (node (ref "SENSOR2") (pin "6") (pinfunction "VDDIO_6") (pintype "power_in"))
      (node (ref "SENSOR2") (pin "8") (pinfunction "VDD_8") (pintype "power_in"))
      (node (ref "U2") (pin "17") (pinfunction "IO19_17") (pintype "bidirectional"))
    )
    (net (code "16") (name "INT_RTC") (class "Default")
      (node (ref "R1-PINH1") (pin "1") (pinfunction "1_1") (pintype "passive"))
      (node (ref "TP15") (pin "TP") (pinfunction "TP_TP") (pintype "input"))
      (node (ref "U2") (pin "8") (pinfunction "IO0_8") (pintype "bidirectional"))
      (node (ref "U3") (pin "3") (pinfunction "SQW/~{INT}_3") (pintype "output"))
    )
    (net (code "17") (name "IO{slash}BOOT") (class "Default")
      (node (ref "BOOT_BUTTON") (pin "3") (pinfunction "3_3") (pintype "passive"))
      (node (ref "BOOT_BUTTON") (pin "4") (pinfunction "4_4") (pintype "passive"))
      (node (ref "C6") (pin "1") (pinfunction "1_1") (pintype "passive"))
      (node (ref "R_BOOT") (pin "1") (pinfunction "1_1") (pintype "passive"))
      (node (ref "U2") (pin "15") (pinfunction "IO9_15") (pintype "bidirectional"))
    )
    (net (code "18") (name "IO{slash}CHANGE") (class "Default")
      (node (ref "C10") (pin "1") (pinfunction "1_1") (pintype "passive"))
      (node (ref "CHANGE_BUTTON") (pin "3") (pinfunction "3_3") (pintype "passive"))
      (node (ref "CHANGE_BUTTON") (pin "4") (pinfunction "4_4") (pintype "passive"))
      (node (ref "R_CHANGE") (pin "1") (pinfunction "1_1") (pintype "passive"))
      (node (ref "U2") (pin "23") (pinfunction "IO15_23") (pintype "bidirectional"))
    )
    (net (code "19") (name "MISO") (class "Default")
      (node (ref "D12") (pin "2") (pinfunction "2_2") (pintype "passive"))
      (node (ref "J4") (pin "P7") (pinfunction "DAT0_P7") (pintype "bidirectional"))
      (node (ref "R8") (pin "1") (pinfunction "1_1") (pintype "passive"))
      (node (ref "TP6") (pin "TP") (pinfunction "TP_TP") (pintype "input"))
      (node (ref "U1") (pin "2") (pinfunction "DO(IO1)_2") (pintype "bidirectional"))
      (node (ref "U2") (pin "27") (pinfunction "IO2_27") (pintype "bidirectional"))
    )
    (net (code "20") (name "MOSI") (class "Default")
      (node (ref "D11") (pin "2") (pinfunction "2_2") (pintype "passive"))
      (node (ref "J1") (pin "14") (pinfunction "14_14") (pintype "bidirectional"))
      (node (ref "J4") (pin "P3") (pinfunction "CMD_P3") (pintype "bidirectional"))
      (node (ref "R7") (pin "1") (pinfunction "1_1") (pintype "passive"))
      (node (ref "TP7") (pin "TP") (pinfunction "TP_TP") (pintype "input"))
      (node (ref "U1") (pin "5") (pinfunction "DI(IO0)_5") (pintype "bidirectional"))
      (node (ref "U2") (pin "7") (pinfunction "IO7_7") (pintype "bidirectional"))
    )
    (net (code "21") (name "Net-(CHG_LED-PadC)") (class "Default")
      (node (ref "CHG_LED") (pin "C") (pinfunction "C_C") (pintype "passive"))
      (node (ref "R1_BAT") (pin "1") (pinfunction "1_1") (pintype "passive"))
    )
    (net (code "22") (name "Net-(D2-CATHODE)") (class "Default")
      (node (ref "C1_BAT1") (pin "1") (pinfunction "1_1") (pintype "passive"))
      (node (ref "D2") (pin "2") (pinfunction "CATHODE_2") (pintype "bidirectional"))
      (node (ref "IC4") (pin "1") (pinfunction "VIN_1") (pintype "bidirectional"))
      (node (ref "IC4") (pin "3") (pinfunction "CE_3") (pintype "bidirectional"))
      (node (ref "Q1") (pin "2") (pinfunction "S_2") (pintype "bidirectional"))
    )
    (net (code "23") (name "Net-(D3-A)") (class "Default")
      (node (ref "C4") (pin "1") (pinfunction "1_1") (pintype "passive"))
      (node (ref "D3") (pin "1") (pinfunction "A_1") (pintype "bidirectional"))
      (node (ref "D4") (pin "2") (pinfunction "K_2") (pintype "bidirectional"))
    )
    (net (code "24") (name "Net-(D7-CATHODE)") (class "Default")
      (node (ref "D7") (pin "2") (pinfunction "CATHODE_2") (pintype "bidirectional"))
      (node (ref "R_CAPACITOR") (pin "2") (pinfunction "2_2") (pintype "passive"))
    )
    (net (code "25") (name "Net-(EPD_C1-Pad1)") (class "Default")
      (node (ref "EPD_C1") (pin "1") (pinfunction "1_1") (pintype "passive"))
      (node (ref "J1") (pin "4") (pinfunction "4_4") (pintype "bidirectional"))
    )
    (net (code "26") (name "Net-(EPD_C2-Pad1)") (class "Default")
      (node (ref "EPD_C2") (pin "1") (pinfunction "1_1") (pintype "passive"))
      (node (ref "J1") (pin "5") (pinfunction "5_5") (pintype "bidirectional"))
    )
    (net (code "27") (name "Net-(EPD_C6-Pad1)") (class "Default")
      (node (ref "EPD_C6") (pin "1") (pinfunction "1_1") (pintype "passive"))
      (node (ref "J1") (pin "18") (pinfunction "18_18") (pintype "bidirectional"))
    )
    (net (code "28") (name "Net-(EPD_C7-Pad1)") (class "Default")
      (node (ref "EPD_C7") (pin "1") (pinfunction "1_1") (pintype "passive"))
      (node (ref "J1") (pin "19") (pinfunction "19_19") (pintype "bidirectional"))
    )
    (net (code "29") (name "Net-(EPD_C8-Pad1)") (class "Default")
      (node (ref "EPD_C8") (pin "1") (pinfunction "1_1") (pintype "passive"))
      (node (ref "J1") (pin "20") (pinfunction "20_20") (pintype "bidirectional"))
    )
    (net (code "30") (name "Net-(EPD_C10-Pad1)") (class "Default")
      (node (ref "EPD_C10") (pin "1") (pinfunction "1_1") (pintype "passive"))
      (node (ref "J1") (pin "22") (pinfunction "22_22") (pintype "bidirectional"))
    )
    (net (code "31") (name "Net-(EPD_C12-Pad1)") (class "Default")
      (node (ref "EPD_C12") (pin "1") (pinfunction "1_1") (pintype "passive"))
      (node (ref "J1") (pin "24") (pinfunction "24_24") (pintype "bidirectional"))
    )
    (net (code "32") (name "Net-(IC1-CT)") (class "Default")
      (node (ref "C_DELAY") (pin "1") (pinfunction "1_1") (pintype "passive"))
      (node (ref "IC1") (pin "5") (pinfunction "CT_5") (pintype "bidirectional"))
    )
    (net (code "33") (name "Net-(J2-PadA5)") (class "Default")
      (node (ref "J2") (pin "A5") (pinfunction "A5_A5") (pintype "bidirectional"))
      (node (ref "R2-USB1") (pin "2") (pinfunction "2_2") (pintype "passive"))
    )
    (net (code "34") (name "Net-(J2-PadB5)") (class "Default")
      (node (ref "J2") (pin "B5") (pinfunction "B5_B5") (pintype "bidirectional"))
      (node (ref "R2-USB") (pin "1") (pinfunction "1_1") (pintype "passive"))
    )
    (net (code "35") (name "Net-(MCP73831-PROG)") (class "Default")
      (node (ref "MCP73831") (pin "5") (pinfunction "PROG_5") (pintype "input"))
      (node (ref "R2_BAT") (pin "2") (pinfunction "2_2") (pintype "passive"))
    )
    (net (code "36") (name "Net-(MCP73831-STAT)") (class "Default")
      (node (ref "MCP73831") (pin "1") (pinfunction "STAT_1") (pintype "output"))
      (node (ref "R1_BAT") (pin "2") (pinfunction "2_2") (pintype "passive"))
    )
    (net (code "37") (name "PREVGH") (class "Default")
      (node (ref "D5") (pin "2") (pinfunction "K_2") (pintype "bidirectional"))
      (node (ref "EPD_C9") (pin "1") (pinfunction "1_1") (pintype "passive"))
      (node (ref "J1") (pin "21") (pinfunction "21_21") (pintype "bidirectional"))
    )
    (net (code "38") (name "PREVGL") (class "Default")
      (node (ref "D4") (pin "1") (pinfunction "A_1") (pintype "bidirectional"))
      (node (ref "EPD_C11") (pin "1") (pinfunction "1_1") (pintype "passive"))
      (node (ref "J1") (pin "23") (pinfunction "23_23") (pintype "bidirectional"))
    )
    (net (code "39") (name "RESE") (class "Default")
      (node (ref "J1") (pin "3") (pinfunction "3_3") (pintype "bidirectional"))
      (node (ref "Q3") (pin "2") (pinfunction "S_2") (pintype "bidirectional"))
      (node (ref "R3") (pin "2") (pinfunction "2_2") (pintype "passive"))
    )
    (net (code "40") (name "RESE'") (class "Default")
      (node (ref "R2") (pin "2") (pinfunction "2_2") (pintype "passive"))
      (node (ref "R3") (pin "1") (pinfunction "1_1") (pintype "passive"))
      (node (ref "SJ1") (pin "2") (pinfunction "2_2") (pintype "passive"))
    )
    (net (code "41") (name "RESET") (class "Default")
      (node (ref "C5") (pin "1") (pinfunction "1_1") (pintype "passive"))
      (node (ref "IC1") (pin "1") (pinfunction "VOUT_1") (pintype "bidirectional"))
      (node (ref "RESET_BUTTON") (pin "3") (pinfunction "3_3") (pintype "passive"))
      (node (ref "RESET_BUTTON") (pin "4") (pinfunction "4_4") (pintype "passive"))
      (node (ref "R_RESET") (pin "1") (pinfunction "1_1") (pintype "passive"))
      (node (ref "U2") (pin "3") (pinfunction "EN_3") (pintype "input"))
    )
    (net (code "42") (name "RTC_RST") (class "Default")
      (node (ref "U2") (pin "16") (pinfunction "IO18_16") (pintype "bidirectional"))
      (node (ref "U3") (pin "4") (pinfunction "~{RST}_4") (pintype "input"))
    )
    (net (code "43") (name "RX") (class "Default")
      (node (ref "TP2") (pin "TP") (pinfunction "TP_TP") (pintype "input"))
      (node (ref "U2") (pin "24") (pinfunction "RXD0/GPIO17_24") (pintype "bidirectional"))
    )
    (net (code "44") (name "SCK") (class "Default")
      (node (ref "D10") (pin "2") (pinfunction "2_2") (pintype "passive"))
      (node (ref "J1") (pin "13") (pinfunction "13_13") (pintype "bidirectional"))
      (node (ref "J4") (pin "P5") (pinfunction "CLK_P5") (pintype "bidirectional"))
      (node (ref "R6") (pin "1") (pinfunction "1_1") (pintype "passive"))
      (node (ref "TP8") (pin "TP") (pinfunction "TP_TP") (pintype "input"))
      (node (ref "U1") (pin "6") (pinfunction "CLK_6") (pintype "input"))
      (node (ref "U2") (pin "6") (pinfunction "IO6_6") (pintype "bidirectional"))
    )
    (net (code "45") (name "SCL") (class "Default")
      (node (ref "J3") (pin "4") (pinfunction "4_4") (pintype "passive"))
      (node (ref "R2-PINH") (pin "1") (pinfunction "1_1") (pintype "passive"))
      (node (ref "SENSOR2") (pin "4") (pinfunction "SCK_4") (pintype "input"))
      (node (ref "U2") (pin "20") (pinfunction "IO22_20") (pintype "bidirectional"))
      (node (ref "U3") (pin "16") (pinfunction "SCL_16") (pintype "input"))
      (node (ref "U4") (pin "7") (pinfunction "SCL_7") (pintype "input"))
    )
    (net (code "46") (name "SDA") (class "Default")
      (node (ref "J3") (pin "3") (pinfunction "3_3") (pintype "passive"))
      (node (ref "R1-PINH") (pin "1") (pinfunction "1_1") (pintype "passive"))
      (node (ref "SENSOR2") (pin "3") (pinfunction "SDI_3") (pintype "bidirectional"))
      (node (ref "U2") (pin "19") (pinfunction "IO21_19") (pintype "bidirectional"))
      (node (ref "U3") (pin "15") (pinfunction "SDA_15") (pintype "bidirectional"))
      (node (ref "U4") (pin "8") (pinfunction "SDA_8") (pintype "bidirectional"))
    )
    (net (code "47") (name "SRC") (class "Default")
      (node (ref "C4") (pin "2") (pinfunction "2_2") (pintype "passive"))
      (node (ref "D5") (pin "1") (pinfunction "A_1") (pintype "bidirectional"))
      (node (ref "L1") (pin "1") (pinfunction "1_1") (pintype "passive"))
      (node (ref "Q3") (pin "3") (pinfunction "D_3") (pintype "bidirectional"))
    )
    (net (code "48") (name "SS_SD") (class "Default")
      (node (ref "D8") (pin "2") (pinfunction "2_2") (pintype "passive"))
      (node (ref "J4") (pin "P2") (pinfunction "CD/DAT3_P2") (pintype "bidirectional"))
      (node (ref "R10") (pin "1") (pinfunction "1_1") (pintype "passive"))
      (node (ref "U2") (pin "4") (pinfunction "IO4_4") (pintype "bidirectional"))
    )
    (net (code "49") (name "TX") (class "Default")
      (node (ref "TP1") (pin "TP") (pinfunction "TP_TP") (pintype "input"))
      (node (ref "U2") (pin "25") (pinfunction "TXD0/GPIO16_25") (pintype "bidirectional"))
    )
    (net (code "50") (name "USB_D+") (class "Default")
      (node (ref "D1") (pin "4") (pinfunction "I/O2_2_4") (pintype "bidirectional"))
      (node (ref "U2") (pin "14") (pinfunction "IO13_14") (pintype "bidirectional"))
    )
    (net (code "51") (name "USB_D-") (class "Default")
      (node (ref "D1") (pin "6") (pinfunction "I/O1_2_6") (pintype "bidirectional"))
      (node (ref "U2") (pin "13") (pinfunction "IO12_13") (pintype "bidirectional"))
    )
    (net (code "52") (name "VBAT") (class "Default")
      (node (ref "C2_BAT") (pin "1") (pinfunction "1_1") (pintype "passive"))
      (node (ref "MCP73831") (pin "3") (pinfunction "VBAT_3") (pintype "power_in"))
      (node (ref "Q1") (pin "3") (pinfunction "D_3") (pintype "bidirectional"))
      (node (ref "TP3") (pin "TP") (pinfunction "TP_TP") (pintype "input"))
      (node (ref "U4") (pin "2") (pinfunction "CELL_2") (pintype "power_in"))
      (node (ref "U4") (pin "3") (pinfunction "VDD_3") (pintype "power_in"))
    )
    (net (code "53") (name "VBUS") (class "Default")
      (node (ref "C1_BAT") (pin "1") (pinfunction "1_1") (pintype "passive"))
      (node (ref "C4_USB") (pin "1") (pinfunction "1_1") (pintype "passive"))
      (node (ref "C5_USB") (pin "1") (pinfunction "1_1") (pintype "passive"))
      (node (ref "CHG_LED") (pin "A") (pinfunction "A_A") (pintype "passive"))
      (node (ref "D1") (pin "2") (pinfunction "GND_2") (pintype "bidirectional"))
      (node (ref "D2") (pin "1") (pinfunction "ANODE_1") (pintype "bidirectional"))
      (node (ref "MCP73831") (pin "4") (pinfunction "VIN_4") (pintype "power_in"))
      (node (ref "PFMF.050.1") (pin "1") (pinfunction "1_1") (pintype "passive"))
      (node (ref "Q1") (pin "1") (pinfunction "G_1") (pintype "bidirectional"))
      (node (ref "R1_PWRUSB") (pin "2") (pinfunction "2_2") (pintype "passive"))
      (node (ref "TP14") (pin "TP") (pinfunction "TP_TP") (pintype "input"))
    )
    (net (code "54") (name "VRTC") (class "Default")
      (node (ref "C10_SUPERCAP") (pin "2") (pinfunction "2_2") (pintype "passive"))
      (node (ref "C8") (pin "1") (pinfunction "1_1") (pintype "passive"))
      (node (ref "R_CAPACITOR") (pin "1") (pinfunction "1_1") (pintype "passive"))
      (node (ref "U3") (pin "14") (pinfunction "VBAT_14") (pintype "power_in"))
    )
    (net (code "55") (name "VUSB") (class "Default")
      (node (ref "J2") (pin "A4") (pinfunction "A4_A4") (pintype "bidirectional"))
      (node (ref "J2") (pin "A9") (pinfunction "A9_A9") (pintype "bidirectional"))
      (node (ref "J2") (pin "B4") (pinfunction "B4_B4") (pintype "bidirectional"))
      (node (ref "J2") (pin "B9") (pinfunction "B9_B9") (pintype "bidirectional"))
      (node (ref "PFMF.050.1") (pin "2") (pinfunction "2_2") (pintype "passive"))
    )
    (net (code "56") (name "unconnected-(IC1-NC-Pad4)") (class "Default")
      (node (ref "IC1") (pin "4") (pinfunction "NC_4") (pintype "no_connect"))
    )
    (net (code "57") (name "unconnected-(IC4-NC-Pad4)") (class "Default")
      (node (ref "IC4") (pin "4") (pinfunction "NC_4") (pintype "no_connect"))
    )
    (net (code "58") (name "unconnected-(J1-Pad1)") (class "Default")
      (node (ref "J1") (pin "1") (pinfunction "1_1") (pintype "bidirectional"))
    )
    (net (code "59") (name "unconnected-(J1-Pad6)") (class "Default")
      (node (ref "J1") (pin "6") (pinfunction "6_6") (pintype "bidirectional"))
    )
    (net (code "60") (name "unconnected-(J1-Pad7)") (class "Default")
      (node (ref "J1") (pin "7") (pinfunction "7_7") (pintype "bidirectional"))
    )
    (net (code "61") (name "unconnected-(J2-PadA8)") (class "Default")
      (node (ref "J2") (pin "A8") (pinfunction "A8_A8") (pintype "bidirectional"))
    )
    (net (code "62") (name "unconnected-(J2-PadB8)") (class "Default")
      (node (ref "J2") (pin "B8") (pinfunction "B8_B8") (pintype "bidirectional"))
    )
    (net (code "63") (name "unconnected-(J4-DAT1-PadP8)") (class "Default")
      (node (ref "J4") (pin "P8") (pinfunction "DAT1_P8") (pintype "bidirectional"))
    )
    (net (code "64") (name "unconnected-(J4-DAT2-PadP1)") (class "Default")
      (node (ref "J4") (pin "P1") (pinfunction "DAT2_P1") (pintype "bidirectional"))
    )
    (net (code "65") (name "unconnected-(J4-DETECTION_1-PadS1)") (class "Default")
      (node (ref "J4") (pin "S1") (pinfunction "DETECTION_1_S1") (pintype "bidirectional"))
    )
    (net (code "66") (name "unconnected-(J4-DETECTION_2-PadS2)") (class "Default")
      (node (ref "J4") (pin "S2") (pinfunction "DETECTION_2_S2") (pintype "bidirectional"))
    )
    (net (code "67") (name "unconnected-(U2-NC-Pad22)") (class "Default")
      (node (ref "U2") (pin "22") (pinfunction "NC_22") (pintype "no_connect"))
    )
    (net (code "68") (name "unconnected-(U4-~{ALERT}-Pad5)") (class "Default")
      (node (ref "U4") (pin "5") (pinfunction "~{ALERT}_5") (pintype "output"))
    )
  )
)
